# v4_bluetooth-20x20_trace-antenna_dc-dc.net
KiCad netlist of a schematic drawn in EAGLE
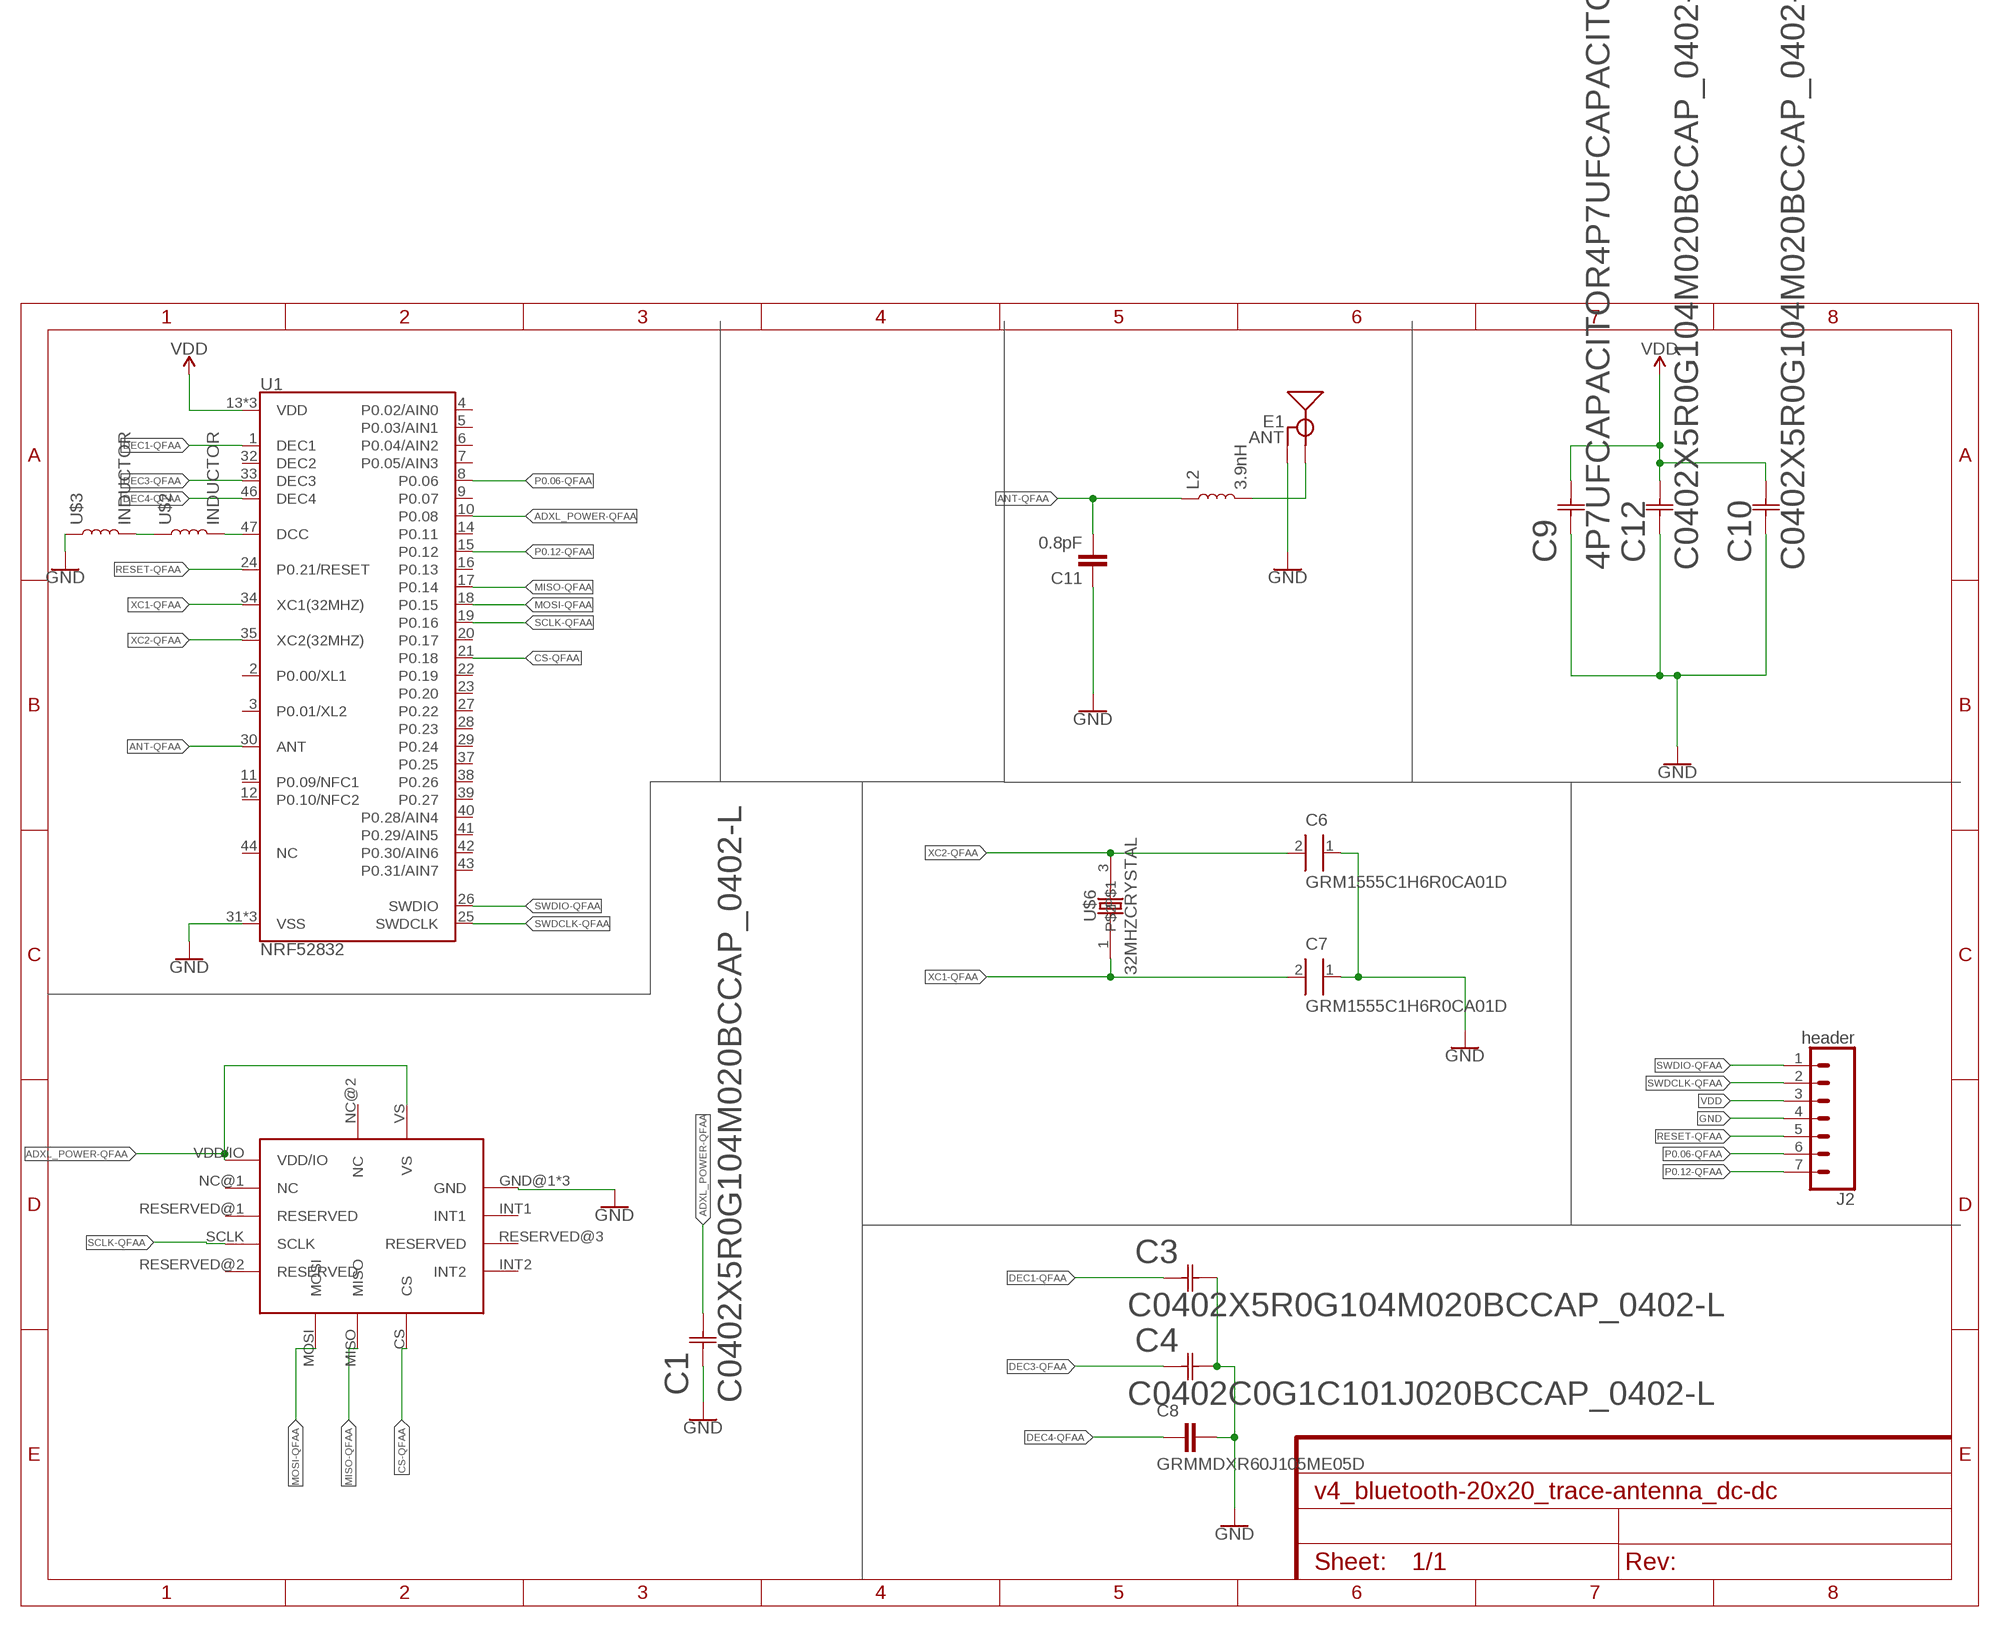
[diagram p0: schematic, sheet 1]

(export (version "E")
  (design (tool "Eeschema 10.0.6"))
  (components
    (comp (ref "C1")
      (value "C0402X5R0G104M020BCCAP_0402-L")
      (footprint "eagle-import:CAP_0402-L")
      (fields (field (name "MANUFACTURER_PART_NUMBER") "C0402C0G1C101J020BC"))
      (libsource (lib "eagle-import") (part "C0402X5R0G104M020BCCAP_0402-L"))
    )
    (comp (ref "C3")
      (value "C0402X5R0G104M020BCCAP_0402-L")
      (footprint "eagle-import:CAP_0402-L")
      (fields (field (name "MANUFACTURER_PART_NUMBER") "C0402C0G1C101J020BC"))
      (libsource (lib "eagle-import") (part "C0402X5R0G104M020BCCAP_0402-L"))
    )
    (comp (ref "C4")
      (value "C0402C0G1C101J020BCCAP_0402-L")
      (footprint "eagle-import:CAP_0402-L")
      (fields (field (name "MANUFACTURER_PART_NUMBER") "C0402C0G1C101J020BC"))
      (libsource (lib "eagle-import") (part "C0402C0G1C101J020BCCAP_0402-L"))
    )
    (comp (ref "C6")
      (value "GRM1555C1H6R0CA01D")
      (footprint "eagle-import:CAPC1005X55N")
      (fields (field (name "DIGI-KEY_PART_NUMBER") "490-8222-1-ND") (field (name "MF") "Murata"))
      (libsource (lib "eagle-import") (part "GRM1555C1H6R0CA01D"))
    )
    (comp (ref "C7")
      (value "GRM1555C1H6R0CA01D")
      (footprint "eagle-import:CAPC1005X55N")
      (fields (field (name "DIGI-KEY_PART_NUMBER") "490-8222-1-ND") (field (name "MF") "Murata"))
      (libsource (lib "eagle-import") (part "GRM1555C1H6R0CA01D"))
    )
    (comp (ref "C8")
      (value "GRMMDXR60J105ME05D")
      (footprint "eagle-import:CAPC0502X28N")
      (fields (field (name "DIGI-KEY_PART_NUMBER") "490-13424-1-ND") (field (name "MF") "Murata"))
      (libsource (lib "eagle-import") (part "GRMMDXR60J105ME05D"))
    )
    (comp (ref "C9")
      (value "4P7UFCAPACITOR4P7UFCAPACITOR")
      (footprint "eagle-import:4P7UFCAPACITOR")
      (fields (field (name "MANUFACTURER_PART_NUMBER") "C0816X5R0J475M050AC"))
      (libsource (lib "eagle-import") (part "4P7UFCAPACITOR4P7UFCAPACITOR"))
    )
    (comp (ref "C10")
      (value "C0402X5R0G104M020BCCAP_0402-L")
      (footprint "eagle-import:CAP_0402-L")
      (fields (field (name "MANUFACTURER_PART_NUMBER") "C0402C0G1C101J020BC"))
      (libsource (lib "eagle-import") (part "C0402X5R0G104M020BCCAP_0402-L"))
    )
    (comp (ref "C11")
      (value "0.8pF")
      (footprint "eagle-import:0402")
      (libsource (lib "eagle-import") (part "0.8PF-0402-50V-0.1PF"))
    )
    (comp (ref "C12")
      (value "C0402X5R0G104M020BCCAP_0402-L")
      (footprint "eagle-import:CAP_0402-L")
      (fields (field (name "MANUFACTURER_PART_NUMBER") "C0402C0G1C101J020BC"))
      (libsource (lib "eagle-import") (part "C0402X5R0G104M020BCCAP_0402-L"))
    )
    (comp (ref "E1")
      (value "ANT")
      (footprint "eagle-import:TRACE_ANTENNA_2.4GHZ_15.2MM")
      (libsource (lib "eagle-import") (part "ANTENNA-GROUNDEDTRACE-15.2MM"))
    )
    (comp (ref "J2")
      (value "header")
      (footprint "eagle-import:1X07")
      (libsource (lib "eagle-import") (part "CONN_07"))
    )
    (comp (ref "L2")
      (value "3.9nH")
      (footprint "eagle-import:0402")
      (libsource (lib "eagle-import") (part "INDUCTOR-0402-3.9NH"))
    )
    (comp (ref "U$1")
      (value "ADXL362")
      (footprint "eagle-import:TFLGA-16_3.3MMX3.1MM")
      (libsource (lib "eagle-import") (part "ADXL362"))
    )
    (comp (ref "U$2")
      (value "INDUCTOR")
      (footprint "eagle-import:0402")
      (libsource (lib "eagle-import") (part "INDUCTOR"))
    )
    (comp (ref "U$3")
      (value "INDUCTOR")
      (footprint "eagle-import:0402")
      (libsource (lib "eagle-import") (part "INDUCTOR"))
    )
    (comp (ref "U$6")
      (value "32MHZCRYSTAL")
      (footprint "eagle-import:32MHZCRYSTAL")
      (libsource (lib "eagle-import") (part "32MHZCRYSTAL"))
    )
    (comp (ref "U1")
      (value "NRF52832")
      (footprint "eagle-import:QFN48-6X6MM")
      (libsource (lib "eagle-import") (part "NRF52832"))
    )
  )
  (nets
    (net (code "1") (name "ADXL_POWER-QFAA") (class "Default")
      (node (ref "C1") (pin "2") (pinfunction "22_2") (pintype "passive"))
      (node (ref "U$1") (pin "VDD/IO") (pinfunction "VDD/IO_VDD/IO") (pintype "bidirectional"))
      (node (ref "U$1") (pin "VS") (pinfunction "VS_VS") (pintype "bidirectional"))
      (node (ref "U1") (pin "10") (pinfunction "P0.08_10") (pintype "bidirectional"))
    )
    (net (code "2") (name "ANT-QFAA") (class "Default")
      (node (ref "C11") (pin "2") (pinfunction "2_2") (pintype "passive"))
      (node (ref "L2") (pin "1") (pinfunction "1_1") (pintype "passive"))
      (node (ref "U1") (pin "30") (pinfunction "ANT_30") (pintype "bidirectional"))
    )
    (net (code "3") (name "CS-QFAA") (class "Default")
      (node (ref "U$1") (pin "CS") (pinfunction "CS_CS") (pintype "bidirectional"))
      (node (ref "U1") (pin "21") (pinfunction "P0.18_21") (pintype "bidirectional"))
    )
    (net (code "4") (name "DEC1-QFAA") (class "Default")
      (node (ref "C3") (pin "1") (pinfunction "11_1") (pintype "passive"))
      (node (ref "U1") (pin "1") (pinfunction "DEC1_1") (pintype "bidirectional"))
    )
    (net (code "5") (name "DEC3-QFAA") (class "Default")
      (node (ref "C4") (pin "1") (pinfunction "11_1") (pintype "passive"))
      (node (ref "U1") (pin "33") (pinfunction "DEC3_33") (pintype "bidirectional"))
    )
    (net (code "6") (name "DEC4-QFAA") (class "Default")
      (node (ref "C8") (pin "1") (pinfunction "1_1") (pintype "passive"))
      (node (ref "U1") (pin "46") (pinfunction "DEC4_46") (pintype "bidirectional"))
    )
    (net (code "7") (name "GND") (class "Default")
      (node (ref "C1") (pin "1") (pinfunction "11_1") (pintype "passive"))
      (node (ref "C10") (pin "1") (pinfunction "11_1") (pintype "passive"))
      (node (ref "C11") (pin "1") (pinfunction "1_1") (pintype "passive"))
      (node (ref "C12") (pin "1") (pinfunction "11_1") (pintype "passive"))
      (node (ref "C3") (pin "2") (pinfunction "22_2") (pintype "passive"))
      (node (ref "C4") (pin "2") (pinfunction "22_2") (pintype "passive"))
      (node (ref "C6") (pin "1") (pinfunction "1_1") (pintype "passive"))
      (node (ref "C7") (pin "1") (pinfunction "1_1") (pintype "passive"))
      (node (ref "C8") (pin "2") (pinfunction "2_2") (pintype "passive"))
      (node (ref "C9") (pin "1") (pinfunction "11_1") (pintype "passive"))
      (node (ref "E1") (pin "GND") (pinfunction "GND_GND") (pintype "bidirectional"))
      (node (ref "J2") (pin "4") (pinfunction "4_4") (pintype "passive"))
      (node (ref "U$1") (pin "GND@1") (pinfunction "GND_GND@1") (pintype "bidirectional"))
      (node (ref "U$1") (pin "GND@2") (pinfunction "GND_GND@2") (pintype "bidirectional"))
      (node (ref "U$1") (pin "GND@3") (pinfunction "GND_GND@3") (pintype "bidirectional"))
      (node (ref "U$3") (pin "1") (pinfunction "1_1") (pintype "passive"))
      (node (ref "U1") (pin "31") (pinfunction "VSS_31") (pintype "bidirectional"))
      (node (ref "U1") (pin "45") (pinfunction "VSS_45") (pintype "bidirectional"))
      (node (ref "U1") (pin "EP") (pinfunction "VSS_EP") (pintype "bidirectional"))
    )
    (net (code "8") (name "MISO-QFAA") (class "Default")
      (node (ref "U$1") (pin "MISO") (pinfunction "MISO_MISO") (pintype "bidirectional"))
      (node (ref "U1") (pin "17") (pinfunction "P0.14_17") (pintype "bidirectional"))
    )
    (net (code "9") (name "MOSI-QFAA") (class "Default")
      (node (ref "U$1") (pin "MOSI") (pinfunction "MOSI_MOSI") (pintype "bidirectional"))
      (node (ref "U1") (pin "18") (pinfunction "P0.15_18") (pintype "bidirectional"))
    )
    (net (code "10") (name "Net-(E1-SIGNAL)") (class "Default")
      (node (ref "E1") (pin "ANT") (pinfunction "SIGNAL_ANT") (pintype "bidirectional"))
      (node (ref "L2") (pin "2") (pinfunction "2_2") (pintype "passive"))
    )
    (net (code "11") (name "Net-(U$2-Pad1)") (class "Default")
      (node (ref "U$2") (pin "1") (pinfunction "1_1") (pintype "passive"))
      (node (ref "U$3") (pin "2") (pinfunction "2_2") (pintype "passive"))
    )
    (net (code "12") (name "Net-(U1-DCC)") (class "Default")
      (node (ref "U$2") (pin "2") (pinfunction "2_2") (pintype "passive"))
      (node (ref "U1") (pin "47") (pinfunction "DCC_47") (pintype "bidirectional"))
    )
    (net (code "13") (name "P0.06-QFAA") (class "Default")
      (node (ref "J2") (pin "6") (pinfunction "6_6") (pintype "passive"))
      (node (ref "U1") (pin "8") (pinfunction "P0.06_8") (pintype "bidirectional"))
    )
    (net (code "14") (name "P0.12-QFAA") (class "Default")
      (node (ref "J2") (pin "7") (pinfunction "7_7") (pintype "passive"))
      (node (ref "U1") (pin "15") (pinfunction "P0.12_15") (pintype "bidirectional"))
    )
    (net (code "15") (name "RESET-QFAA") (class "Default")
      (node (ref "J2") (pin "5") (pinfunction "5_5") (pintype "passive"))
      (node (ref "U1") (pin "24") (pinfunction "P0.21/RESET_24") (pintype "bidirectional"))
    )
    (net (code "16") (name "SCLK-QFAA") (class "Default")
      (node (ref "U$1") (pin "SCLK") (pinfunction "SCLK_SCLK") (pintype "bidirectional"))
      (node (ref "U1") (pin "19") (pinfunction "P0.16_19") (pintype "bidirectional"))
    )
    (net (code "17") (name "SWDCLK-QFAA") (class "Default")
      (node (ref "J2") (pin "2") (pinfunction "2_2") (pintype "passive"))
      (node (ref "U1") (pin "25") (pinfunction "SWDCLK_25") (pintype "bidirectional"))
    )
    (net (code "18") (name "SWDIO-QFAA") (class "Default")
      (node (ref "J2") (pin "1") (pinfunction "1_1") (pintype "passive"))
      (node (ref "U1") (pin "26") (pinfunction "SWDIO_26") (pintype "bidirectional"))
    )
    (net (code "19") (name "VDD") (class "Default")
      (node (ref "C10") (pin "2") (pinfunction "22_2") (pintype "passive"))
      (node (ref "C12") (pin "2") (pinfunction "22_2") (pintype "passive"))
      (node (ref "C9") (pin "2") (pinfunction "22_2") (pintype "passive"))
      (node (ref "J2") (pin "3") (pinfunction "3_3") (pintype "passive"))
      (node (ref "U1") (pin "13") (pinfunction "VDD_13") (pintype "bidirectional"))
      (node (ref "U1") (pin "36") (pinfunction "VDD_36") (pintype "bidirectional"))
      (node (ref "U1") (pin "48") (pinfunction "VDD_48") (pintype "bidirectional"))
    )
    (net (code "20") (name "XC1-QFAA") (class "Default")
      (node (ref "C7") (pin "2") (pinfunction "2_2") (pintype "passive"))
      (node (ref "U$6") (pin "1") (pinfunction "P$1_1") (pintype "bidirectional"))
      (node (ref "U1") (pin "34") (pinfunction "XC1(32MHZ)_34") (pintype "bidirectional"))
    )
    (net (code "21") (name "XC2-QFAA") (class "Default")
      (node (ref "C6") (pin "2") (pinfunction "2_2") (pintype "passive"))
      (node (ref "U$6") (pin "3") (pinfunction "P$2_3") (pintype "bidirectional"))
      (node (ref "U1") (pin "35") (pinfunction "XC2(32MHZ)_35") (pintype "bidirectional"))
    )
    (net (code "22") (name "unconnected-(U$1-NC-PadNC@1)") (class "Default")
      (node (ref "U$1") (pin "NC@1") (pinfunction "NC_NC@1") (pintype "bidirectional"))
    )
    (net (code "23") (name "unconnected-(U$1-NC-PadNC@2)") (class "Default")
      (node (ref "U$1") (pin "NC@2") (pinfunction "NC_NC@2") (pintype "bidirectional"))
    )
    (net (code "24") (name "unconnected-(U$1-PadINT1)") (class "Default")
      (node (ref "U$1") (pin "INT1") (pinfunction "INT1_INT1") (pintype "bidirectional"))
    )
    (net (code "25") (name "unconnected-(U$1-PadINT2)") (class "Default")
      (node (ref "U$1") (pin "INT2") (pinfunction "INT2_INT2") (pintype "bidirectional"))
    )
    (net (code "26") (name "unconnected-(U$1-RESERVED-PadRESERVED@1)") (class "Default")
      (node (ref "U$1") (pin "RESERVED@1") (pinfunction "RESERVED_RESERVED@1") (pintype "bidirectional"))
    )
    (net (code "27") (name "unconnected-(U$1-RESERVED-PadRESERVED@2)") (class "Default")
      (node (ref "U$1") (pin "RESERVED@2") (pinfunction "RESERVED_RESERVED@2") (pintype "bidirectional"))
    )
    (net (code "28") (name "unconnected-(U$1-RESERVED-PadRESERVED@3)") (class "Default")
      (node (ref "U$1") (pin "RESERVED@3") (pinfunction "RESERVED_RESERVED@3") (pintype "bidirectional"))
    )
    (net (code "29") (name "unconnected-(U1-DEC2-Pad32)") (class "Default")
      (node (ref "U1") (pin "32") (pinfunction "DEC2_32") (pintype "bidirectional"))
    )
    (net (code "30") (name "unconnected-(U1-NC-Pad44)") (class "Default")
      (node (ref "U1") (pin "44") (pinfunction "NC_44") (pintype "bidirectional"))
    )
    (net (code "31") (name "unconnected-(U1-P0.00{slash}XL1-Pad2)") (class "Default")
      (node (ref "U1") (pin "2") (pinfunction "P0.00/XL1_2") (pintype "bidirectional"))
    )
    (net (code "32") (name "unconnected-(U1-P0.01{slash}XL2-Pad3)") (class "Default")
      (node (ref "U1") (pin "3") (pinfunction "P0.01/XL2_3") (pintype "bidirectional"))
    )
    (net (code "33") (name "unconnected-(U1-P0.02{slash}AIN0-Pad4)") (class "Default")
      (node (ref "U1") (pin "4") (pinfunction "P0.02/AIN0_4") (pintype "bidirectional"))
    )
    (net (code "34") (name "unconnected-(U1-P0.03{slash}AIN1-Pad5)") (class "Default")
      (node (ref "U1") (pin "5") (pinfunction "P0.03/AIN1_5") (pintype "bidirectional"))
    )
    (net (code "35") (name "unconnected-(U1-P0.04{slash}AIN2-Pad6)") (class "Default")
      (node (ref "U1") (pin "6") (pinfunction "P0.04/AIN2_6") (pintype "bidirectional"))
    )
    (net (code "36") (name "unconnected-(U1-P0.05{slash}AIN3-Pad7)") (class "Default")
      (node (ref "U1") (pin "7") (pinfunction "P0.05/AIN3_7") (pintype "bidirectional"))
    )
    (net (code "37") (name "unconnected-(U1-P0.07-Pad9)") (class "Default")
      (node (ref "U1") (pin "9") (pinfunction "P0.07_9") (pintype "bidirectional"))
    )
    (net (code "38") (name "unconnected-(U1-P0.09{slash}NFC1-Pad11)") (class "Default")
      (node (ref "U1") (pin "11") (pinfunction "P0.09/NFC1_11") (pintype "bidirectional"))
    )
    (net (code "39") (name "unconnected-(U1-P0.10{slash}NFC2-Pad12)") (class "Default")
      (node (ref "U1") (pin "12") (pinfunction "P0.10/NFC2_12") (pintype "bidirectional"))
    )
    (net (code "40") (name "unconnected-(U1-P0.11-Pad14)") (class "Default")
      (node (ref "U1") (pin "14") (pinfunction "P0.11_14") (pintype "bidirectional"))
    )
    (net (code "41") (name "unconnected-(U1-P0.13-Pad16)") (class "Default")
      (node (ref "U1") (pin "16") (pinfunction "P0.13_16") (pintype "bidirectional"))
    )
    (net (code "42") (name "unconnected-(U1-P0.17-Pad20)") (class "Default")
      (node (ref "U1") (pin "20") (pinfunction "P0.17_20") (pintype "bidirectional"))
    )
    (net (code "43") (name "unconnected-(U1-P0.19-Pad22)") (class "Default")
      (node (ref "U1") (pin "22") (pinfunction "P0.19_22") (pintype "bidirectional"))
    )
    (net (code "44") (name "unconnected-(U1-P0.20-Pad23)") (class "Default")
      (node (ref "U1") (pin "23") (pinfunction "P0.20_23") (pintype "bidirectional"))
    )
    (net (code "45") (name "unconnected-(U1-P0.22-Pad27)") (class "Default")
      (node (ref "U1") (pin "27") (pinfunction "P0.22_27") (pintype "bidirectional"))
    )
    (net (code "46") (name "unconnected-(U1-P0.23-Pad28)") (class "Default")
      (node (ref "U1") (pin "28") (pinfunction "P0.23_28") (pintype "bidirectional"))
    )
    (net (code "47") (name "unconnected-(U1-P0.24-Pad29)") (class "Default")
      (node (ref "U1") (pin "29") (pinfunction "P0.24_29") (pintype "bidirectional"))
    )
    (net (code "48") (name "unconnected-(U1-P0.25-Pad37)") (class "Default")
      (node (ref "U1") (pin "37") (pinfunction "P0.25_37") (pintype "bidirectional"))
    )
    (net (code "49") (name "unconnected-(U1-P0.26-Pad38)") (class "Default")
      (node (ref "U1") (pin "38") (pinfunction "P0.26_38") (pintype "bidirectional"))
    )
    (net (code "50") (name "unconnected-(U1-P0.27-Pad39)") (class "Default")
      (node (ref "U1") (pin "39") (pinfunction "P0.27_39") (pintype "bidirectional"))
    )
    (net (code "51") (name "unconnected-(U1-P0.28{slash}AIN4-Pad40)") (class "Default")
      (node (ref "U1") (pin "40") (pinfunction "P0.28/AIN4_40") (pintype "bidirectional"))
    )
    (net (code "52") (name "unconnected-(U1-P0.29{slash}AIN5-Pad41)") (class "Default")
      (node (ref "U1") (pin "41") (pinfunction "P0.29/AIN5_41") (pintype "bidirectional"))
    )
    (net (code "53") (name "unconnected-(U1-P0.30{slash}AIN6-Pad42)") (class "Default")
      (node (ref "U1") (pin "42") (pinfunction "P0.30/AIN6_42") (pintype "bidirectional"))
    )
    (net (code "54") (name "unconnected-(U1-P0.31{slash}AIN7-Pad43)") (class "Default")
      (node (ref "U1") (pin "43") (pinfunction "P0.31/AIN7_43") (pintype "bidirectional"))
    )
  )
)
